# ikea_night_light.net
KiCad netlist of a schematic drawn in EAGLE
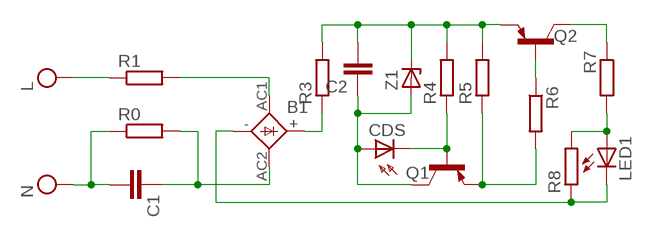
[diagram p0: schematic, sheet 1]

(export (version "E")
  (design (tool "Eeschema 10.0.6"))
  (components
    (comp (ref "B1")
      (value "1KAB")
      (footprint "eagle-import:1KAB")
      (libsource (lib "eagle-import") (part "1KAB"))
    )
    (comp (ref "C1")
      (value "CXXC10B5")
      (footprint "eagle-import:XC10B5")
      (libsource (lib "eagle-import") (part "CXXC10B5"))
    )
    (comp (ref "C2")
      (value "C-EUC0805")
      (footprint "eagle-import:C0805")
      (libsource (lib "eagle-import") (part "C-EUC0805"))
    )
    (comp (ref "CDS")
      (value "BP104")
      (footprint "eagle-import:BP104")
      (fields (field (name "MF") "VISHAY/TELEFUNKEN"))
      (libsource (lib "eagle-import") (part "BP104"))
    )
    (comp (ref "LED1")
      (value "LED10MM")
      (footprint "eagle-import:LED10MM")
      (libsource (lib "eagle-import") (part "LED10MM"))
    )
    (comp (ref "Q1")
      (value "-PNP-SOT23-BCE")
      (footprint "eagle-import:SOT23-BCE")
      (libsource (lib "eagle-import") (part "-PNP-SOT23-BCE"))
    )
    (comp (ref "Q2")
      (value "-PNP-SOT23-BCE")
      (footprint "eagle-import:SOT23-BCE")
      (libsource (lib "eagle-import") (part "-PNP-SOT23-BCE"))
    )
    (comp (ref "R0")
      (value "R-EU_M0805")
      (footprint "eagle-import:M0805")
      (libsource (lib "eagle-import") (part "R-EU_M0805"))
    )
    (comp (ref "R1")
      (value "R-EU_M0805")
      (footprint "eagle-import:M0805")
      (libsource (lib "eagle-import") (part "R-EU_M0805"))
    )
    (comp (ref "R3")
      (value "R-EU_M0805")
      (footprint "eagle-import:M0805")
      (libsource (lib "eagle-import") (part "R-EU_M0805"))
    )
    (comp (ref "R4")
      (value "R-EU_M0805")
      (footprint "eagle-import:M0805")
      (libsource (lib "eagle-import") (part "R-EU_M0805"))
    )
    (comp (ref "R5")
      (value "R-EU_M0805")
      (footprint "eagle-import:M0805")
      (libsource (lib "eagle-import") (part "R-EU_M0805"))
    )
    (comp (ref "R6")
      (value "R-EU_M0805")
      (footprint "eagle-import:M0805")
      (libsource (lib "eagle-import") (part "R-EU_M0805"))
    )
    (comp (ref "R7")
      (value "R-EU_M0805")
      (footprint "eagle-import:M0805")
      (libsource (lib "eagle-import") (part "R-EU_M0805"))
    )
    (comp (ref "R8")
      (value "R-EU_M0805")
      (footprint "eagle-import:M0805")
      (libsource (lib "eagle-import") (part "R-EU_M0805"))
    )
    (comp (ref "Z1")
      (value "1N5333")
      (footprint "eagle-import:C1702-15")
      (libsource (lib "eagle-import") (part "1N5333"))
    )
  )
  (nets
    (net (code "1") (name "L") (class "Default")
      (node (ref "C1") (pin "2") (pinfunction "2_2") (pintype "passive"))
      (node (ref "R0") (pin "1") (pinfunction "1_1") (pintype "passive"))
      (node (ref "R1") (pin "1") (pinfunction "1_1") (pintype "passive"))
    )
    (net (code "2") (name "Net-(B1-Pad+)") (class "Default")
      (node (ref "B1") (pin "+") (pinfunction "+_+") (pintype "passive"))
      (node (ref "R3") (pin "1") (pinfunction "1_1") (pintype "passive"))
    )
    (net (code "3") (name "Net-(B1-PadAC1)") (class "Default")
      (node (ref "B1") (pin "AC1") (pinfunction "AC1_AC1") (pintype "passive"))
      (node (ref "R1") (pin "2") (pinfunction "2_2") (pintype "passive"))
    )
    (net (code "4") (name "Net-(B1-PadAC2)") (class "Default")
      (node (ref "B1") (pin "AC2") (pinfunction "AC2_AC2") (pintype "passive"))
      (node (ref "C1") (pin "1") (pinfunction "1_1") (pintype "passive"))
      (node (ref "R0") (pin "2") (pinfunction "2_2") (pintype "passive"))
    )
    (net (code "5") (name "Net-(C2-Pad1)") (class "Default")
      (node (ref "C2") (pin "1") (pinfunction "1_1") (pintype "passive"))
      (node (ref "CDS") (pin "A") (pinfunction "A_A") (pintype "passive"))
      (node (ref "Q1") (pin "C") (pinfunction "C_C") (pintype "passive"))
      (node (ref "Z1") (pin "A") (pinfunction "A_A") (pintype "passive"))
    )
    (net (code "6") (name "Net-(C2-Pad2)") (class "Default")
      (node (ref "C2") (pin "2") (pinfunction "2_2") (pintype "passive"))
      (node (ref "Q2") (pin "E") (pinfunction "E_E") (pintype "passive"))
      (node (ref "R3") (pin "2") (pinfunction "2_2") (pintype "passive"))
      (node (ref "R4") (pin "2") (pinfunction "2_2") (pintype "passive"))
      (node (ref "R5") (pin "2") (pinfunction "2_2") (pintype "passive"))
      (node (ref "Z1") (pin "C") (pinfunction "C_C") (pintype "passive"))
    )
    (net (code "7") (name "Net-(CDS-C)") (class "Default")
      (node (ref "CDS") (pin "K") (pinfunction "C_K") (pintype "passive"))
      (node (ref "Q1") (pin "B") (pinfunction "B_B") (pintype "passive"))
      (node (ref "R4") (pin "1") (pinfunction "1_1") (pintype "passive"))
    )
    (net (code "8") (name "Net-(LED1-C)") (class "Default")
      (node (ref "B1") (pin "-") (pinfunction "-_-") (pintype "passive"))
      (node (ref "LED1") (pin "K") (pinfunction "C_K") (pintype "passive"))
      (node (ref "R8") (pin "1") (pinfunction "1_1") (pintype "passive"))
    )
    (net (code "9") (name "Net-(LED1-PadA)") (class "Default")
      (node (ref "LED1") (pin "A") (pinfunction "A_A") (pintype "passive"))
      (node (ref "R7") (pin "2") (pinfunction "2_2") (pintype "passive"))
      (node (ref "R8") (pin "2") (pinfunction "2_2") (pintype "passive"))
    )
    (net (code "10") (name "Net-(Q1-PadE)") (class "Default")
      (node (ref "Q1") (pin "E") (pinfunction "E_E") (pintype "passive"))
      (node (ref "R5") (pin "1") (pinfunction "1_1") (pintype "passive"))
      (node (ref "R6") (pin "2") (pinfunction "2_2") (pintype "passive"))
    )
    (net (code "11") (name "Net-(Q2-PadB)") (class "Default")
      (node (ref "Q2") (pin "B") (pinfunction "B_B") (pintype "passive"))
      (node (ref "R6") (pin "1") (pinfunction "1_1") (pintype "passive"))
    )
    (net (code "12") (name "Net-(Q2-PadC)") (class "Default")
      (node (ref "Q2") (pin "C") (pinfunction "C_C") (pintype "passive"))
      (node (ref "R7") (pin "1") (pinfunction "1_1") (pintype "passive"))
    )
  )
)
